# SiPM_16Ch_Sc3.net
KiCad netlist of a schematic drawn in Altium Designer
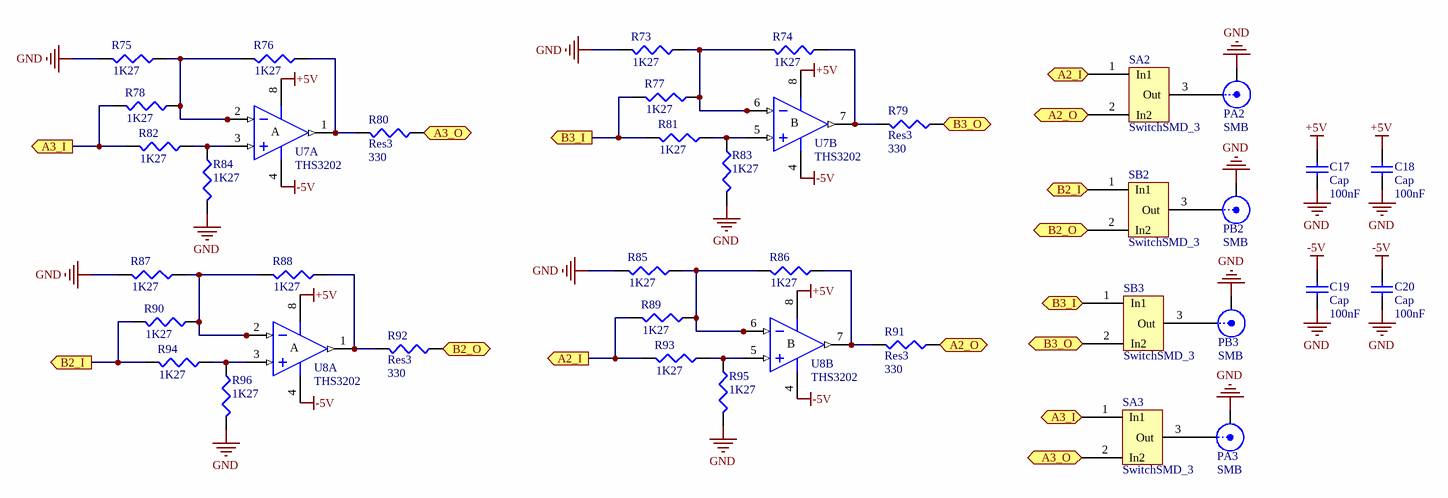
[diagram p0: SiPM_16Ch_Sc3.SchDoc]

(export (version "E")
  (design (tool "Eeschema 10.0.6"))
  (components
    (comp (ref "C17")
      (value "Cap")
      (footprint "1608[0603]")
      (description "Capacitor")
      (fields (field (name "ALTIUM_VALUE") "100nF") (field (name "PUBLISHER") "Altium Limited"))
      (libsource (lib "Miscellaneous Devices") (part "Cap"))
    )
    (comp (ref "C18")
      (value "Cap")
      (footprint "1608[0603]")
      (description "Capacitor")
      (fields (field (name "ALTIUM_VALUE") "100nF") (field (name "PUBLISHER") "Altium Limited"))
      (libsource (lib "Miscellaneous Devices") (part "Cap"))
    )
    (comp (ref "C19")
      (value "Cap")
      (footprint "1608[0603]")
      (description "Capacitor")
      (fields (field (name "ALTIUM_VALUE") "100nF") (field (name "PUBLISHER") "Altium Limited"))
      (libsource (lib "Miscellaneous Devices") (part "Cap"))
    )
    (comp (ref "C20")
      (value "Cap")
      (footprint "1608[0603]")
      (description "Capacitor")
      (fields (field (name "ALTIUM_VALUE") "100nF") (field (name "PUBLISHER") "Altium Limited"))
      (libsource (lib "Miscellaneous Devices") (part "Cap"))
    )
    (comp (ref "PA2")
      (value "SMB")
      (footprint "SMB_V-RJ45")
      (description "SMB Straight Connector")
      (fields (field (name "PUBLISHER") "Altium Limited"))
      (libsource (lib "Miscellaneous Connectors") (part "SMB"))
    )
    (comp (ref "PA3")
      (value "SMB")
      (footprint "SMB_V-RJ45")
      (description "SMB Straight Connector")
      (fields (field (name "PUBLISHER") "Altium Limited"))
      (libsource (lib "Miscellaneous Connectors") (part "SMB"))
    )
    (comp (ref "PB2")
      (value "SMB")
      (footprint "SMB_V-RJ45")
      (description "SMB Straight Connector")
      (fields (field (name "PUBLISHER") "Altium Limited"))
      (libsource (lib "Miscellaneous Connectors") (part "SMB"))
    )
    (comp (ref "PB3")
      (value "SMB")
      (footprint "SMB_V-RJ45")
      (description "SMB Straight Connector")
      (fields (field (name "PUBLISHER") "Altium Limited"))
      (libsource (lib "Miscellaneous Connectors") (part "SMB"))
    )
    (comp (ref "R73")
      (value "1K27")
      (footprint "J1-0603")
      (description "Resistor")
      (fields (field (name "Comment") "Res3") (field (name "PUBLISHER") "Altium Limited"))
      (libsource (lib "Miscellaneous Devices") (part "Res3"))
    )
    (comp (ref "R74")
      (value "1K27")
      (footprint "J1-0603")
      (description "Resistor")
      (fields (field (name "Comment") "Res3") (field (name "PUBLISHER") "Altium Limited"))
      (libsource (lib "Miscellaneous Devices") (part "Res3"))
    )
    (comp (ref "R75")
      (value "1K27")
      (footprint "J1-0603")
      (description "Resistor")
      (fields (field (name "Comment") "Res3") (field (name "PUBLISHER") "Altium Limited"))
      (libsource (lib "Miscellaneous Devices") (part "Res3"))
    )
    (comp (ref "R76")
      (value "1K27")
      (footprint "J1-0603")
      (description "Resistor")
      (fields (field (name "Comment") "Res3") (field (name "PUBLISHER") "Altium Limited"))
      (libsource (lib "Miscellaneous Devices") (part "Res3"))
    )
    (comp (ref "R77")
      (value "1K27")
      (footprint "J1-0603")
      (description "Resistor")
      (fields (field (name "Comment") "Res3") (field (name "PUBLISHER") "Altium Limited"))
      (libsource (lib "Miscellaneous Devices") (part "Res3"))
    )
    (comp (ref "R78")
      (value "1K27")
      (footprint "J1-0603")
      (description "Resistor")
      (fields (field (name "Comment") "Res3") (field (name "PUBLISHER") "Altium Limited"))
      (libsource (lib "Miscellaneous Devices") (part "Res3"))
    )
    (comp (ref "R79")
      (value "Res3")
      (footprint "J1-0603")
      (description "Resistor")
      (fields (field (name "ALTIUM_VALUE") "330") (field (name "PUBLISHER") "Altium Limited"))
      (libsource (lib "Miscellaneous Devices") (part "Res3"))
    )
    (comp (ref "R80")
      (value "Res3")
      (footprint "J1-0603")
      (description "Resistor")
      (fields (field (name "ALTIUM_VALUE") "330") (field (name "PUBLISHER") "Altium Limited"))
      (libsource (lib "Miscellaneous Devices") (part "Res3"))
    )
    (comp (ref "R81")
      (value "1K27")
      (footprint "J1-0603")
      (description "Resistor")
      (fields (field (name "Comment") "Res3") (field (name "PUBLISHER") "Altium Limited"))
      (libsource (lib "Miscellaneous Devices") (part "Res3"))
    )
    (comp (ref "R82")
      (value "1K27")
      (footprint "J1-0603")
      (description "Resistor")
      (fields (field (name "Comment") "Res3") (field (name "PUBLISHER") "Altium Limited"))
      (libsource (lib "Miscellaneous Devices") (part "Res3"))
    )
    (comp (ref "R83")
      (value "1K27")
      (footprint "J1-0603")
      (description "Resistor")
      (fields (field (name "Comment") "Res3") (field (name "PUBLISHER") "Altium Limited"))
      (libsource (lib "Miscellaneous Devices") (part "Res3"))
    )
    (comp (ref "R84")
      (value "1K27")
      (footprint "J1-0603")
      (description "Resistor")
      (fields (field (name "Comment") "Res3") (field (name "PUBLISHER") "Altium Limited"))
      (libsource (lib "Miscellaneous Devices") (part "Res3"))
    )
    (comp (ref "R85")
      (value "1K27")
      (footprint "J1-0603")
      (description "Resistor")
      (fields (field (name "Comment") "Res3") (field (name "PUBLISHER") "Altium Limited"))
      (libsource (lib "Miscellaneous Devices") (part "Res3"))
    )
    (comp (ref "R86")
      (value "1K27")
      (footprint "J1-0603")
      (description "Resistor")
      (fields (field (name "Comment") "Res3") (field (name "PUBLISHER") "Altium Limited"))
      (libsource (lib "Miscellaneous Devices") (part "Res3"))
    )
    (comp (ref "R87")
      (value "1K27")
      (footprint "J1-0603")
      (description "Resistor")
      (fields (field (name "Comment") "Res3") (field (name "PUBLISHER") "Altium Limited"))
      (libsource (lib "Miscellaneous Devices") (part "Res3"))
    )
    (comp (ref "R88")
      (value "1K27")
      (footprint "J1-0603")
      (description "Resistor")
      (fields (field (name "Comment") "Res3") (field (name "PUBLISHER") "Altium Limited"))
      (libsource (lib "Miscellaneous Devices") (part "Res3"))
    )
    (comp (ref "R89")
      (value "1K27")
      (footprint "J1-0603")
      (description "Resistor")
      (fields (field (name "Comment") "Res3") (field (name "PUBLISHER") "Altium Limited"))
      (libsource (lib "Miscellaneous Devices") (part "Res3"))
    )
    (comp (ref "R90")
      (value "1K27")
      (footprint "J1-0603")
      (description "Resistor")
      (fields (field (name "Comment") "Res3") (field (name "PUBLISHER") "Altium Limited"))
      (libsource (lib "Miscellaneous Devices") (part "Res3"))
    )
    (comp (ref "R91")
      (value "Res3")
      (footprint "J1-0603")
      (description "Resistor")
      (fields (field (name "ALTIUM_VALUE") "330") (field (name "PUBLISHER") "Altium Limited"))
      (libsource (lib "Miscellaneous Devices") (part "Res3"))
    )
    (comp (ref "R92")
      (value "Res3")
      (footprint "J1-0603")
      (description "Resistor")
      (fields (field (name "ALTIUM_VALUE") "330") (field (name "PUBLISHER") "Altium Limited"))
      (libsource (lib "Miscellaneous Devices") (part "Res3"))
    )
    (comp (ref "R93")
      (value "1K27")
      (footprint "J1-0603")
      (description "Resistor")
      (fields (field (name "Comment") "Res3") (field (name "PUBLISHER") "Altium Limited"))
      (libsource (lib "Miscellaneous Devices") (part "Res3"))
    )
    (comp (ref "R94")
      (value "1K27")
      (footprint "J1-0603")
      (description "Resistor")
      (fields (field (name "Comment") "Res3") (field (name "PUBLISHER") "Altium Limited"))
      (libsource (lib "Miscellaneous Devices") (part "Res3"))
    )
    (comp (ref "R95")
      (value "1K27")
      (footprint "J1-0603")
      (description "Resistor")
      (fields (field (name "Comment") "Res3") (field (name "PUBLISHER") "Altium Limited"))
      (libsource (lib "Miscellaneous Devices") (part "Res3"))
    )
    (comp (ref "R96")
      (value "1K27")
      (footprint "J1-0603")
      (description "Resistor")
      (fields (field (name "Comment") "Res3") (field (name "PUBLISHER") "Altium Limited"))
      (libsource (lib "Miscellaneous Devices") (part "Res3"))
    )
    (comp (ref "SA2")
      (value "SwitchSMD_3")
      (footprint "SwitchSMD_0603")
      (libsource (lib "Int_Lib1") (part "SwitchSMD_3"))
    )
    (comp (ref "SA3")
      (value "SwitchSMD_3")
      (footprint "SwitchSMD_0603")
      (libsource (lib "Int_Lib1") (part "SwitchSMD_3"))
    )
    (comp (ref "SB2")
      (value "SwitchSMD_3")
      (footprint "SwitchSMD_0603")
      (libsource (lib "Int_Lib1") (part "SwitchSMD_3"))
    )
    (comp (ref "SB3")
      (value "SwitchSMD_3")
      (footprint "SwitchSMD_0603")
      (libsource (lib "Int_Lib1") (part "SwitchSMD_3"))
    )
    (comp (ref "U7")
      (value "THS3202")
      (footprint "SO-8_M")
      (description "Dual 600MHz, 50mW Current Feedback Amplifier")
      (fields (field (name "PUBLISHER") "Altium Limited"))
      (libsource (lib "AD Operational Amplifier") (part "AD8002AR"))
    )
    (comp (ref "U8")
      (value "THS3202")
      (footprint "SO-8_M")
      (description "Dual 600MHz, 50mW Current Feedback Amplifier")
      (fields (field (name "PUBLISHER") "Altium Limited"))
      (libsource (lib "AD Operational Amplifier") (part "AD8002AR"))
    )
  )
  (nets
    (net (code "1") (name "+5V") (class "Default")
      (node (ref "C17") (pin "2") (pinfunction "2_2") (pintype "passive"))
      (node (ref "C18") (pin "2") (pinfunction "2_2") (pintype "passive"))
      (node (ref "U7") (pin "8") (pinfunction "V+_8") (pintype "power_in"))
      (node (ref "U8") (pin "8") (pinfunction "V+_8") (pintype "power_in"))
    )
    (net (code "2") (name "-5V") (class "Default")
      (node (ref "C19") (pin "2") (pinfunction "2_2") (pintype "passive"))
      (node (ref "C20") (pin "2") (pinfunction "2_2") (pintype "passive"))
      (node (ref "U7") (pin "4") (pinfunction "V-_4") (pintype "power_in"))
      (node (ref "U8") (pin "4") (pinfunction "V-_4") (pintype "power_in"))
    )
    (net (code "3") (name "/A2_I") (class "Default")
      (node (ref "R89") (pin "2") (pinfunction "2_2") (pintype "passive"))
      (node (ref "R93") (pin "2") (pinfunction "2_2") (pintype "passive"))
      (node (ref "SA2") (pin "1") (pinfunction "In1_1") (pintype "passive"))
    )
    (net (code "4") (name "/A2_O") (class "Default")
      (node (ref "R91") (pin "1") (pinfunction "1_1") (pintype "passive"))
      (node (ref "SA2") (pin "2") (pinfunction "In2_2") (pintype "passive"))
    )
    (net (code "5") (name "/A3_I") (class "Default")
      (node (ref "R78") (pin "2") (pinfunction "2_2") (pintype "passive"))
      (node (ref "R82") (pin "2") (pinfunction "2_2") (pintype "passive"))
      (node (ref "SA3") (pin "1") (pinfunction "In1_1") (pintype "passive"))
    )
    (net (code "6") (name "/A3_O") (class "Default")
      (node (ref "R80") (pin "1") (pinfunction "1_1") (pintype "passive"))
      (node (ref "SA3") (pin "2") (pinfunction "In2_2") (pintype "passive"))
    )
    (net (code "7") (name "/B2_I") (class "Default")
      (node (ref "R90") (pin "2") (pinfunction "2_2") (pintype "passive"))
      (node (ref "R94") (pin "2") (pinfunction "2_2") (pintype "passive"))
      (node (ref "SB2") (pin "1") (pinfunction "In1_1") (pintype "passive"))
    )
    (net (code "8") (name "/B2_O") (class "Default")
      (node (ref "R92") (pin "1") (pinfunction "1_1") (pintype "passive"))
      (node (ref "SB2") (pin "2") (pinfunction "In2_2") (pintype "passive"))
    )
    (net (code "9") (name "/B3_I") (class "Default")
      (node (ref "R77") (pin "2") (pinfunction "2_2") (pintype "passive"))
      (node (ref "R81") (pin "2") (pinfunction "2_2") (pintype "passive"))
      (node (ref "SB3") (pin "1") (pinfunction "In1_1") (pintype "passive"))
    )
    (net (code "10") (name "/B3_O") (class "Default")
      (node (ref "R79") (pin "1") (pinfunction "1_1") (pintype "passive"))
      (node (ref "SB3") (pin "2") (pinfunction "In2_2") (pintype "passive"))
    )
    (net (code "11") (name "GND") (class "Default")
      (node (ref "C17") (pin "1") (pinfunction "1_1") (pintype "passive"))
      (node (ref "C18") (pin "1") (pinfunction "1_1") (pintype "passive"))
      (node (ref "C19") (pin "1") (pinfunction "1_1") (pintype "passive"))
      (node (ref "C20") (pin "1") (pinfunction "1_1") (pintype "passive"))
      (node (ref "PA2") (pin "2") (pinfunction "Y_2") (pintype "passive"))
      (node (ref "PA3") (pin "2") (pinfunction "Y_2") (pintype "passive"))
      (node (ref "PB2") (pin "2") (pinfunction "Y_2") (pintype "passive"))
      (node (ref "PB3") (pin "2") (pinfunction "Y_2") (pintype "passive"))
      (node (ref "R73") (pin "2") (pinfunction "2_2") (pintype "passive"))
      (node (ref "R75") (pin "2") (pinfunction "2_2") (pintype "passive"))
      (node (ref "R83") (pin "2") (pinfunction "2_2") (pintype "passive"))
      (node (ref "R84") (pin "2") (pinfunction "2_2") (pintype "passive"))
      (node (ref "R85") (pin "2") (pinfunction "2_2") (pintype "passive"))
      (node (ref "R87") (pin "2") (pinfunction "2_2") (pintype "passive"))
      (node (ref "R95") (pin "2") (pinfunction "2_2") (pintype "passive"))
      (node (ref "R96") (pin "2") (pinfunction "2_2") (pintype "passive"))
    )
    (net (code "12") (name "Net-(PA2-X)") (class "Default")
      (node (ref "PA2") (pin "1") (pinfunction "X_1") (pintype "passive"))
      (node (ref "SA2") (pin "3") (pinfunction "Out_3") (pintype "passive"))
    )
    (net (code "13") (name "Net-(PA3-X)") (class "Default")
      (node (ref "PA3") (pin "1") (pinfunction "X_1") (pintype "passive"))
      (node (ref "SA3") (pin "3") (pinfunction "Out_3") (pintype "passive"))
    )
    (net (code "14") (name "Net-(PB2-X)") (class "Default")
      (node (ref "PB2") (pin "1") (pinfunction "X_1") (pintype "passive"))
      (node (ref "SB2") (pin "3") (pinfunction "Out_3") (pintype "passive"))
    )
    (net (code "15") (name "Net-(PB3-X)") (class "Default")
      (node (ref "PB3") (pin "1") (pinfunction "X_1") (pintype "passive"))
      (node (ref "SB3") (pin "3") (pinfunction "Out_3") (pintype "passive"))
    )
    (net (code "16") (name "Net-(U7A-IN+)") (class "Default")
      (node (ref "R82") (pin "1") (pinfunction "1_1") (pintype "passive"))
      (node (ref "R84") (pin "1") (pinfunction "1_1") (pintype "passive"))
      (node (ref "U7") (pin "3") (pinfunction "IN+_3") (pintype "input"))
    )
    (net (code "17") (name "Net-(U7A-IN-)") (class "Default")
      (node (ref "R75") (pin "1") (pinfunction "1_1") (pintype "passive"))
      (node (ref "R76") (pin "2") (pinfunction "2_2") (pintype "passive"))
      (node (ref "R78") (pin "1") (pinfunction "1_1") (pintype "passive"))
      (node (ref "U7") (pin "2") (pinfunction "IN-_2") (pintype "input"))
    )
    (net (code "18") (name "Net-(U7A-OUT)") (class "Default")
      (node (ref "R76") (pin "1") (pinfunction "1_1") (pintype "passive"))
      (node (ref "R80") (pin "2") (pinfunction "2_2") (pintype "passive"))
      (node (ref "U7") (pin "1") (pinfunction "OUT_1") (pintype "output"))
    )
    (net (code "19") (name "Net-(U7B-IN+)") (class "Default")
      (node (ref "R81") (pin "1") (pinfunction "1_1") (pintype "passive"))
      (node (ref "R83") (pin "1") (pinfunction "1_1") (pintype "passive"))
      (node (ref "U7") (pin "5") (pinfunction "IN+_5") (pintype "input"))
    )
    (net (code "20") (name "Net-(U7B-IN-)") (class "Default")
      (node (ref "R73") (pin "1") (pinfunction "1_1") (pintype "passive"))
      (node (ref "R74") (pin "2") (pinfunction "2_2") (pintype "passive"))
      (node (ref "R77") (pin "1") (pinfunction "1_1") (pintype "passive"))
      (node (ref "U7") (pin "6") (pinfunction "IN-_6") (pintype "input"))
    )
    (net (code "21") (name "Net-(U7B-OUT)") (class "Default")
      (node (ref "R74") (pin "1") (pinfunction "1_1") (pintype "passive"))
      (node (ref "R79") (pin "2") (pinfunction "2_2") (pintype "passive"))
      (node (ref "U7") (pin "7") (pinfunction "OUT_7") (pintype "output"))
    )
    (net (code "22") (name "Net-(U8A-IN+)") (class "Default")
      (node (ref "R94") (pin "1") (pinfunction "1_1") (pintype "passive"))
      (node (ref "R96") (pin "1") (pinfunction "1_1") (pintype "passive"))
      (node (ref "U8") (pin "3") (pinfunction "IN+_3") (pintype "input"))
    )
    (net (code "23") (name "Net-(U8A-IN-)") (class "Default")
      (node (ref "R87") (pin "1") (pinfunction "1_1") (pintype "passive"))
      (node (ref "R88") (pin "2") (pinfunction "2_2") (pintype "passive"))
      (node (ref "R90") (pin "1") (pinfunction "1_1") (pintype "passive"))
      (node (ref "U8") (pin "2") (pinfunction "IN-_2") (pintype "input"))
    )
    (net (code "24") (name "Net-(U8A-OUT)") (class "Default")
      (node (ref "R88") (pin "1") (pinfunction "1_1") (pintype "passive"))
      (node (ref "R92") (pin "2") (pinfunction "2_2") (pintype "passive"))
      (node (ref "U8") (pin "1") (pinfunction "OUT_1") (pintype "output"))
    )
    (net (code "25") (name "Net-(U8B-IN+)") (class "Default")
      (node (ref "R93") (pin "1") (pinfunction "1_1") (pintype "passive"))
      (node (ref "R95") (pin "1") (pinfunction "1_1") (pintype "passive"))
      (node (ref "U8") (pin "5") (pinfunction "IN+_5") (pintype "input"))
    )
    (net (code "26") (name "Net-(U8B-IN-)") (class "Default")
      (node (ref "R85") (pin "1") (pinfunction "1_1") (pintype "passive"))
      (node (ref "R86") (pin "2") (pinfunction "2_2") (pintype "passive"))
      (node (ref "R89") (pin "1") (pinfunction "1_1") (pintype "passive"))
      (node (ref "U8") (pin "6") (pinfunction "IN-_6") (pintype "input"))
    )
    (net (code "27") (name "Net-(U8B-OUT)") (class "Default")
      (node (ref "R86") (pin "1") (pinfunction "1_1") (pintype "passive"))
      (node (ref "R91") (pin "2") (pinfunction "2_2") (pintype "passive"))
      (node (ref "U8") (pin "7") (pinfunction "OUT_7") (pintype "output"))
    )
  )
)
